# PWM_Generation.net
KiCad netlist of a schematic drawn in Altium Designer
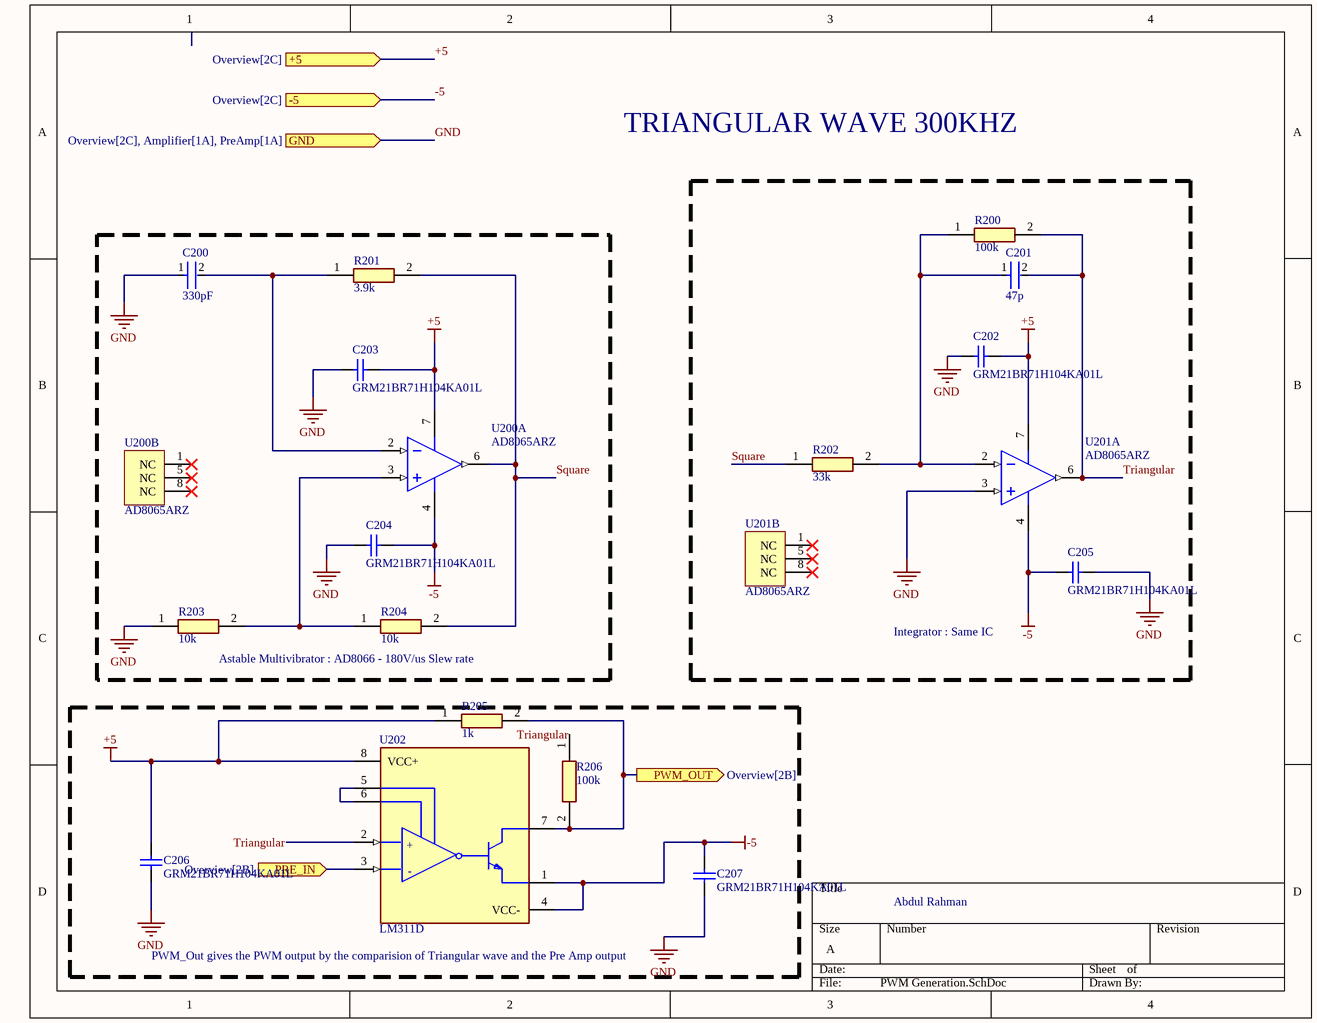
[diagram p0: PWM Generation.SchDoc]

(export (version "E")
  (design (tool "Eeschema 10.0.6"))
  (components
    (comp (ref "C200")
      (value "330pF")
      (footprint "FP-RCE1K1-3_15-MFG")
      (description "Capacitor")
      (libsource (lib "Altium Content Vault") (part "02cd4be3c70576c341d710602a673aa"))
    )
    (comp (ref "C201")
      (value "47p")
      (footprint "FP-RCE1K1-3_15-MFG")
      (description "Capacitor")
      (libsource (lib "Altium Content Vault") (part "02cd4be3c70576c341d710602a673aa"))
    )
    (comp (ref "C202")
      (value "GRM21BR71H104KA01L")
      (footprint "CAPC2013X135X45ML10T25")
      (description "Chip Capacitor, 0.1 uF, +/- 10%, 50 V, -55 to 125 degC, 0805 (2012 Metric), RoHS, Tape and Reel")
      (fields (field (name "VOLTAGE") "50V") (field (name "TOLERANCE") "10%"))
      (libsource (lib "Altium Content Vault") (part "CAP-NP-2"))
    )
    (comp (ref "C203")
      (value "GRM21BR71H104KA01L")
      (footprint "CAPC2013X135X45ML10T25")
      (description "Chip Capacitor, 0.1 uF, +/- 10%, 50 V, -55 to 125 degC, 0805 (2012 Metric), RoHS, Tape and Reel")
      (fields (field (name "VOLTAGE") "50V") (field (name "TOLERANCE") "10%"))
      (libsource (lib "Altium Content Vault") (part "CAP-NP-2"))
    )
    (comp (ref "C204")
      (value "GRM21BR71H104KA01L")
      (footprint "CAPC2013X135X45ML10T25")
      (description "Chip Capacitor, 0.1 uF, +/- 10%, 50 V, -55 to 125 degC, 0805 (2012 Metric), RoHS, Tape and Reel")
      (fields (field (name "VOLTAGE") "50V") (field (name "TOLERANCE") "10%"))
      (libsource (lib "Altium Content Vault") (part "CAP-NP-2"))
    )
    (comp (ref "C205")
      (value "GRM21BR71H104KA01L")
      (footprint "CAPC2013X135X45ML10T25")
      (description "Chip Capacitor, 0.1 uF, +/- 10%, 50 V, -55 to 125 degC, 0805 (2012 Metric), RoHS, Tape and Reel")
      (fields (field (name "VOLTAGE") "50V") (field (name "TOLERANCE") "10%"))
      (libsource (lib "Altium Content Vault") (part "CAP-NP-2"))
    )
    (comp (ref "C206")
      (value "GRM21BR71H104KA01L")
      (footprint "CAPC2013X135X45ML10T25")
      (description "Chip Capacitor, 0.1 uF, +/- 10%, 50 V, -55 to 125 degC, 0805 (2012 Metric), RoHS, Tape and Reel")
      (fields (field (name "VOLTAGE") "50V") (field (name "TOLERANCE") "10%"))
      (libsource (lib "Altium Content Vault") (part "CAP-NP-2"))
    )
    (comp (ref "C207")
      (value "GRM21BR71H104KA01L")
      (footprint "CAPC2013X135X45ML10T25")
      (description "Chip Capacitor, 0.1 uF, +/- 10%, 50 V, -55 to 125 degC, 0805 (2012 Metric), RoHS, Tape and Reel")
      (fields (field (name "VOLTAGE") "50V") (field (name "TOLERANCE") "10%"))
      (libsource (lib "Altium Content Vault") (part "CAP-NP-2"))
    )
    (comp (ref "R200")
      (value "100k")
      (footprint "RESAD1650W60L650D250")
      (description "Resistor")
      (fields
        (field (name "MANUFACTURER_PART_NUMBER") "PR01000101001JR500")
        (field (name "MOUSER PART NUMBER") "594-5073NW1K000J")
      )
      (libsource (lib "Schlib1") (part "PR01000101001JR500"))
    )
    (comp (ref "R201")
      (value "3.9k")
      (footprint "RESAD1650W60L650D250")
      (description "Resistor")
      (fields
        (field (name "MANUFACTURER_PART_NUMBER") "PR01000101001JR500")
        (field (name "MOUSER PART NUMBER") "594-5073NW1K000J")
      )
      (libsource (lib "Schlib1") (part "PR01000101001JR500"))
    )
    (comp (ref "R202")
      (value "33k")
      (footprint "RESAD1650W60L650D250")
      (description "Resistor")
      (fields
        (field (name "MANUFACTURER_PART_NUMBER") "PR01000101001JR500")
        (field (name "MOUSER PART NUMBER") "594-5073NW1K000J")
      )
      (libsource (lib "Schlib1") (part "PR01000101001JR500"))
    )
    (comp (ref "R203")
      (value "10k")
      (footprint "RESAD1650W60L650D250")
      (description "Resistor")
      (fields
        (field (name "MANUFACTURER_PART_NUMBER") "PR01000101001JR500")
        (field (name "MOUSER PART NUMBER") "594-5073NW1K000J")
      )
      (libsource (lib "Schlib1") (part "PR01000101001JR500"))
    )
    (comp (ref "R204")
      (value "10k")
      (footprint "RESAD1650W60L650D250")
      (description "Resistor")
      (fields
        (field (name "MANUFACTURER_PART_NUMBER") "PR01000101001JR500")
        (field (name "MOUSER PART NUMBER") "594-5073NW1K000J")
      )
      (libsource (lib "Schlib1") (part "PR01000101001JR500"))
    )
    (comp (ref "R205")
      (value "1k")
      (footprint "RESAD1650W60L650D250")
      (description "Resistor")
      (fields
        (field (name "MANUFACTURER_PART_NUMBER") "PR01000101001JR500")
        (field (name "MOUSER PART NUMBER") "594-5073NW1K000J")
      )
      (libsource (lib "Schlib1") (part "PR01000101001JR500"))
    )
    (comp (ref "R206")
      (value "100k")
      (footprint "RESAD1650W60L650D250")
      (description "Resistor")
      (fields
        (field (name "MANUFACTURER_PART_NUMBER") "PR01000101001JR500")
        (field (name "MOUSER PART NUMBER") "594-5073NW1K000J")
      )
      (libsource (lib "") (part "PR01000101001JR500_1"))
    )
    (comp (ref "U200")
      (value "AD8065ARZ")
      (footprint "ADI-R-8_N")
      (fields (field (name "MANUFACTURER") "Analog Devices") (field (name "GENERIC PART NUMBER") "AD8065"))
      (libsource (lib "Altium Content Vault") (part "ADI-AD8XX-X8"))
    )
    (comp (ref "U201")
      (value "AD8065ARZ")
      (footprint "ADI-R-8_N")
      (fields (field (name "MANUFACTURER") "Analog Devices") (field (name "GENERIC PART NUMBER") "AD8065"))
      (libsource (lib "Altium Content Vault") (part "ADI-AD8XX-X8"))
    )
    (comp (ref "U202")
      (value "LM311D")
      (footprint "FP-D0008A-MFG")
      (description "IC DIFF COMP W/STROBE 8-SOIC")
      (fields
        (field (name "OCTOPART") "https://octopart.com/lm311d-texas+instruments-428348")
        (field (name "MANUFACTURER") "Texas Instruments")
      )
      (libsource (lib "Altium Content Vault") (part "4f14c3e39a10475c26dfba85d01abf5"))
    )
  )
  (nets
    (net (code "1") (name "+5") (class "Default")
      (node (ref "C202") (pin "1") (pinfunction "1_1") (pintype "passive"))
      (node (ref "C203") (pin "1") (pinfunction "1_1") (pintype "passive"))
      (node (ref "C206") (pin "2") (pinfunction "2_2") (pintype "passive"))
      (node (ref "R205") (pin "1") (pinfunction "1_1") (pintype "passive"))
      (node (ref "U200") (pin "7") (pinfunction "+VS_7") (pintype "power_in"))
      (node (ref "U201") (pin "7") (pinfunction "+VS_7") (pintype "power_in"))
      (node (ref "U202") (pin "8") (pinfunction "VCC+_8") (pintype "passive"))
    )
    (net (code "2") (name "-5") (class "Default")
      (node (ref "C204") (pin "1") (pinfunction "1_1") (pintype "passive"))
      (node (ref "C205") (pin "2") (pinfunction "2_2") (pintype "passive"))
      (node (ref "C207") (pin "2") (pinfunction "2_2") (pintype "passive"))
      (node (ref "U200") (pin "4") (pinfunction "-VS_4") (pintype "power_in"))
      (node (ref "U201") (pin "4") (pinfunction "-VS_4") (pintype "power_in"))
      (node (ref "U202") (pin "1") (pinfunction "EMIT_OUT_1") (pintype "passive"))
      (node (ref "U202") (pin "4") (pinfunction "VCC-_4") (pintype "passive"))
    )
    (net (code "3") (name "/PRE_IN") (class "Default")
      (node (ref "U202") (pin "3") (pinfunction "IN-_3") (pintype "input"))
    )
    (net (code "4") (name "/PWM_OUT") (class "Default")
      (node (ref "R205") (pin "2") (pinfunction "2_2") (pintype "passive"))
      (node (ref "R206") (pin "2") (pinfunction "2_2") (pintype "passive"))
      (node (ref "U202") (pin "7") (pinfunction "COL_OUT_7") (pintype "open_collector"))
    )
    (net (code "5") (name "/Square") (class "Default")
      (node (ref "R201") (pin "2") (pinfunction "2_2") (pintype "passive"))
      (node (ref "R202") (pin "1") (pinfunction "1_1") (pintype "passive"))
      (node (ref "R204") (pin "2") (pinfunction "2_2") (pintype "passive"))
      (node (ref "U200") (pin "6") (pinfunction "VOUT_6") (pintype "output"))
    )
    (net (code "6") (name "/Triangular") (class "Default")
      (node (ref "C201") (pin "2") (pinfunction "2_2") (pintype "passive"))
      (node (ref "R200") (pin "2") (pinfunction "2_2") (pintype "passive"))
      (node (ref "R206") (pin "1") (pinfunction "1_1") (pintype "passive"))
      (node (ref "U201") (pin "6") (pinfunction "VOUT_6") (pintype "output"))
      (node (ref "U202") (pin "2") (pinfunction "IN+_2") (pintype "input"))
    )
    (net (code "7") (name "GND") (class "Default")
      (node (ref "C200") (pin "1") (pinfunction "1_1") (pintype "passive"))
      (node (ref "C202") (pin "2") (pinfunction "2_2") (pintype "passive"))
      (node (ref "C203") (pin "2") (pinfunction "2_2") (pintype "passive"))
      (node (ref "C204") (pin "2") (pinfunction "2_2") (pintype "passive"))
      (node (ref "C205") (pin "1") (pinfunction "1_1") (pintype "passive"))
      (node (ref "C206") (pin "1") (pinfunction "1_1") (pintype "passive"))
      (node (ref "C207") (pin "1") (pinfunction "1_1") (pintype "passive"))
      (node (ref "R203") (pin "1") (pinfunction "1_1") (pintype "passive"))
      (node (ref "U201") (pin "3") (pinfunction "+IN_3") (pintype "input"))
    )
    (net (code "8") (name "Net-(U200A-+IN)") (class "Default")
      (node (ref "R203") (pin "2") (pinfunction "2_2") (pintype "passive"))
      (node (ref "R204") (pin "1") (pinfunction "1_1") (pintype "passive"))
      (node (ref "U200") (pin "3") (pinfunction "+IN_3") (pintype "input"))
    )
    (net (code "9") (name "Net-(U200A--IN)") (class "Default")
      (node (ref "C200") (pin "2") (pinfunction "2_2") (pintype "passive"))
      (node (ref "R201") (pin "1") (pinfunction "1_1") (pintype "passive"))
      (node (ref "U200") (pin "2") (pinfunction "-IN_2") (pintype "input"))
    )
    (net (code "10") (name "Net-(U201A--IN)") (class "Default")
      (node (ref "C201") (pin "1") (pinfunction "1_1") (pintype "passive"))
      (node (ref "R200") (pin "1") (pinfunction "1_1") (pintype "passive"))
      (node (ref "R202") (pin "2") (pinfunction "2_2") (pintype "passive"))
      (node (ref "U201") (pin "2") (pinfunction "-IN_2") (pintype "input"))
    )
    (net (code "11") (name "Net-(U202-BALANCE)") (class "Default")
      (node (ref "U202") (pin "5") (pinfunction "BALANCE_5") (pintype "passive"))
      (node (ref "U202") (pin "6") (pinfunction "BAL/STRB_6") (pintype "passive"))
    )
    (net (code "12") (name "unconnected-(U200B-NC-Pad1)") (class "Default")
      (node (ref "U200") (pin "1") (pinfunction "NC_1") (pintype "passive+no_connect"))
    )
    (net (code "13") (name "unconnected-(U200B-NC-Pad5)") (class "Default")
      (node (ref "U200") (pin "5") (pinfunction "NC_5") (pintype "passive+no_connect"))
    )
    (net (code "14") (name "unconnected-(U200B-NC-Pad8)") (class "Default")
      (node (ref "U200") (pin "8") (pinfunction "NC_8") (pintype "passive+no_connect"))
    )
    (net (code "15") (name "unconnected-(U201B-NC-Pad1)") (class "Default")
      (node (ref "U201") (pin "1") (pinfunction "NC_1") (pintype "passive+no_connect"))
    )
    (net (code "16") (name "unconnected-(U201B-NC-Pad5)") (class "Default")
      (node (ref "U201") (pin "5") (pinfunction "NC_5") (pintype "passive+no_connect"))
    )
    (net (code "17") (name "unconnected-(U201B-NC-Pad8)") (class "Default")
      (node (ref "U201") (pin "8") (pinfunction "NC_8") (pintype "passive+no_connect"))
    )
  )
)
